# FLIGHT-CONTROLLER_VERSION_2.net
KiCad netlist of a schematic drawn in EasyEDA Pro
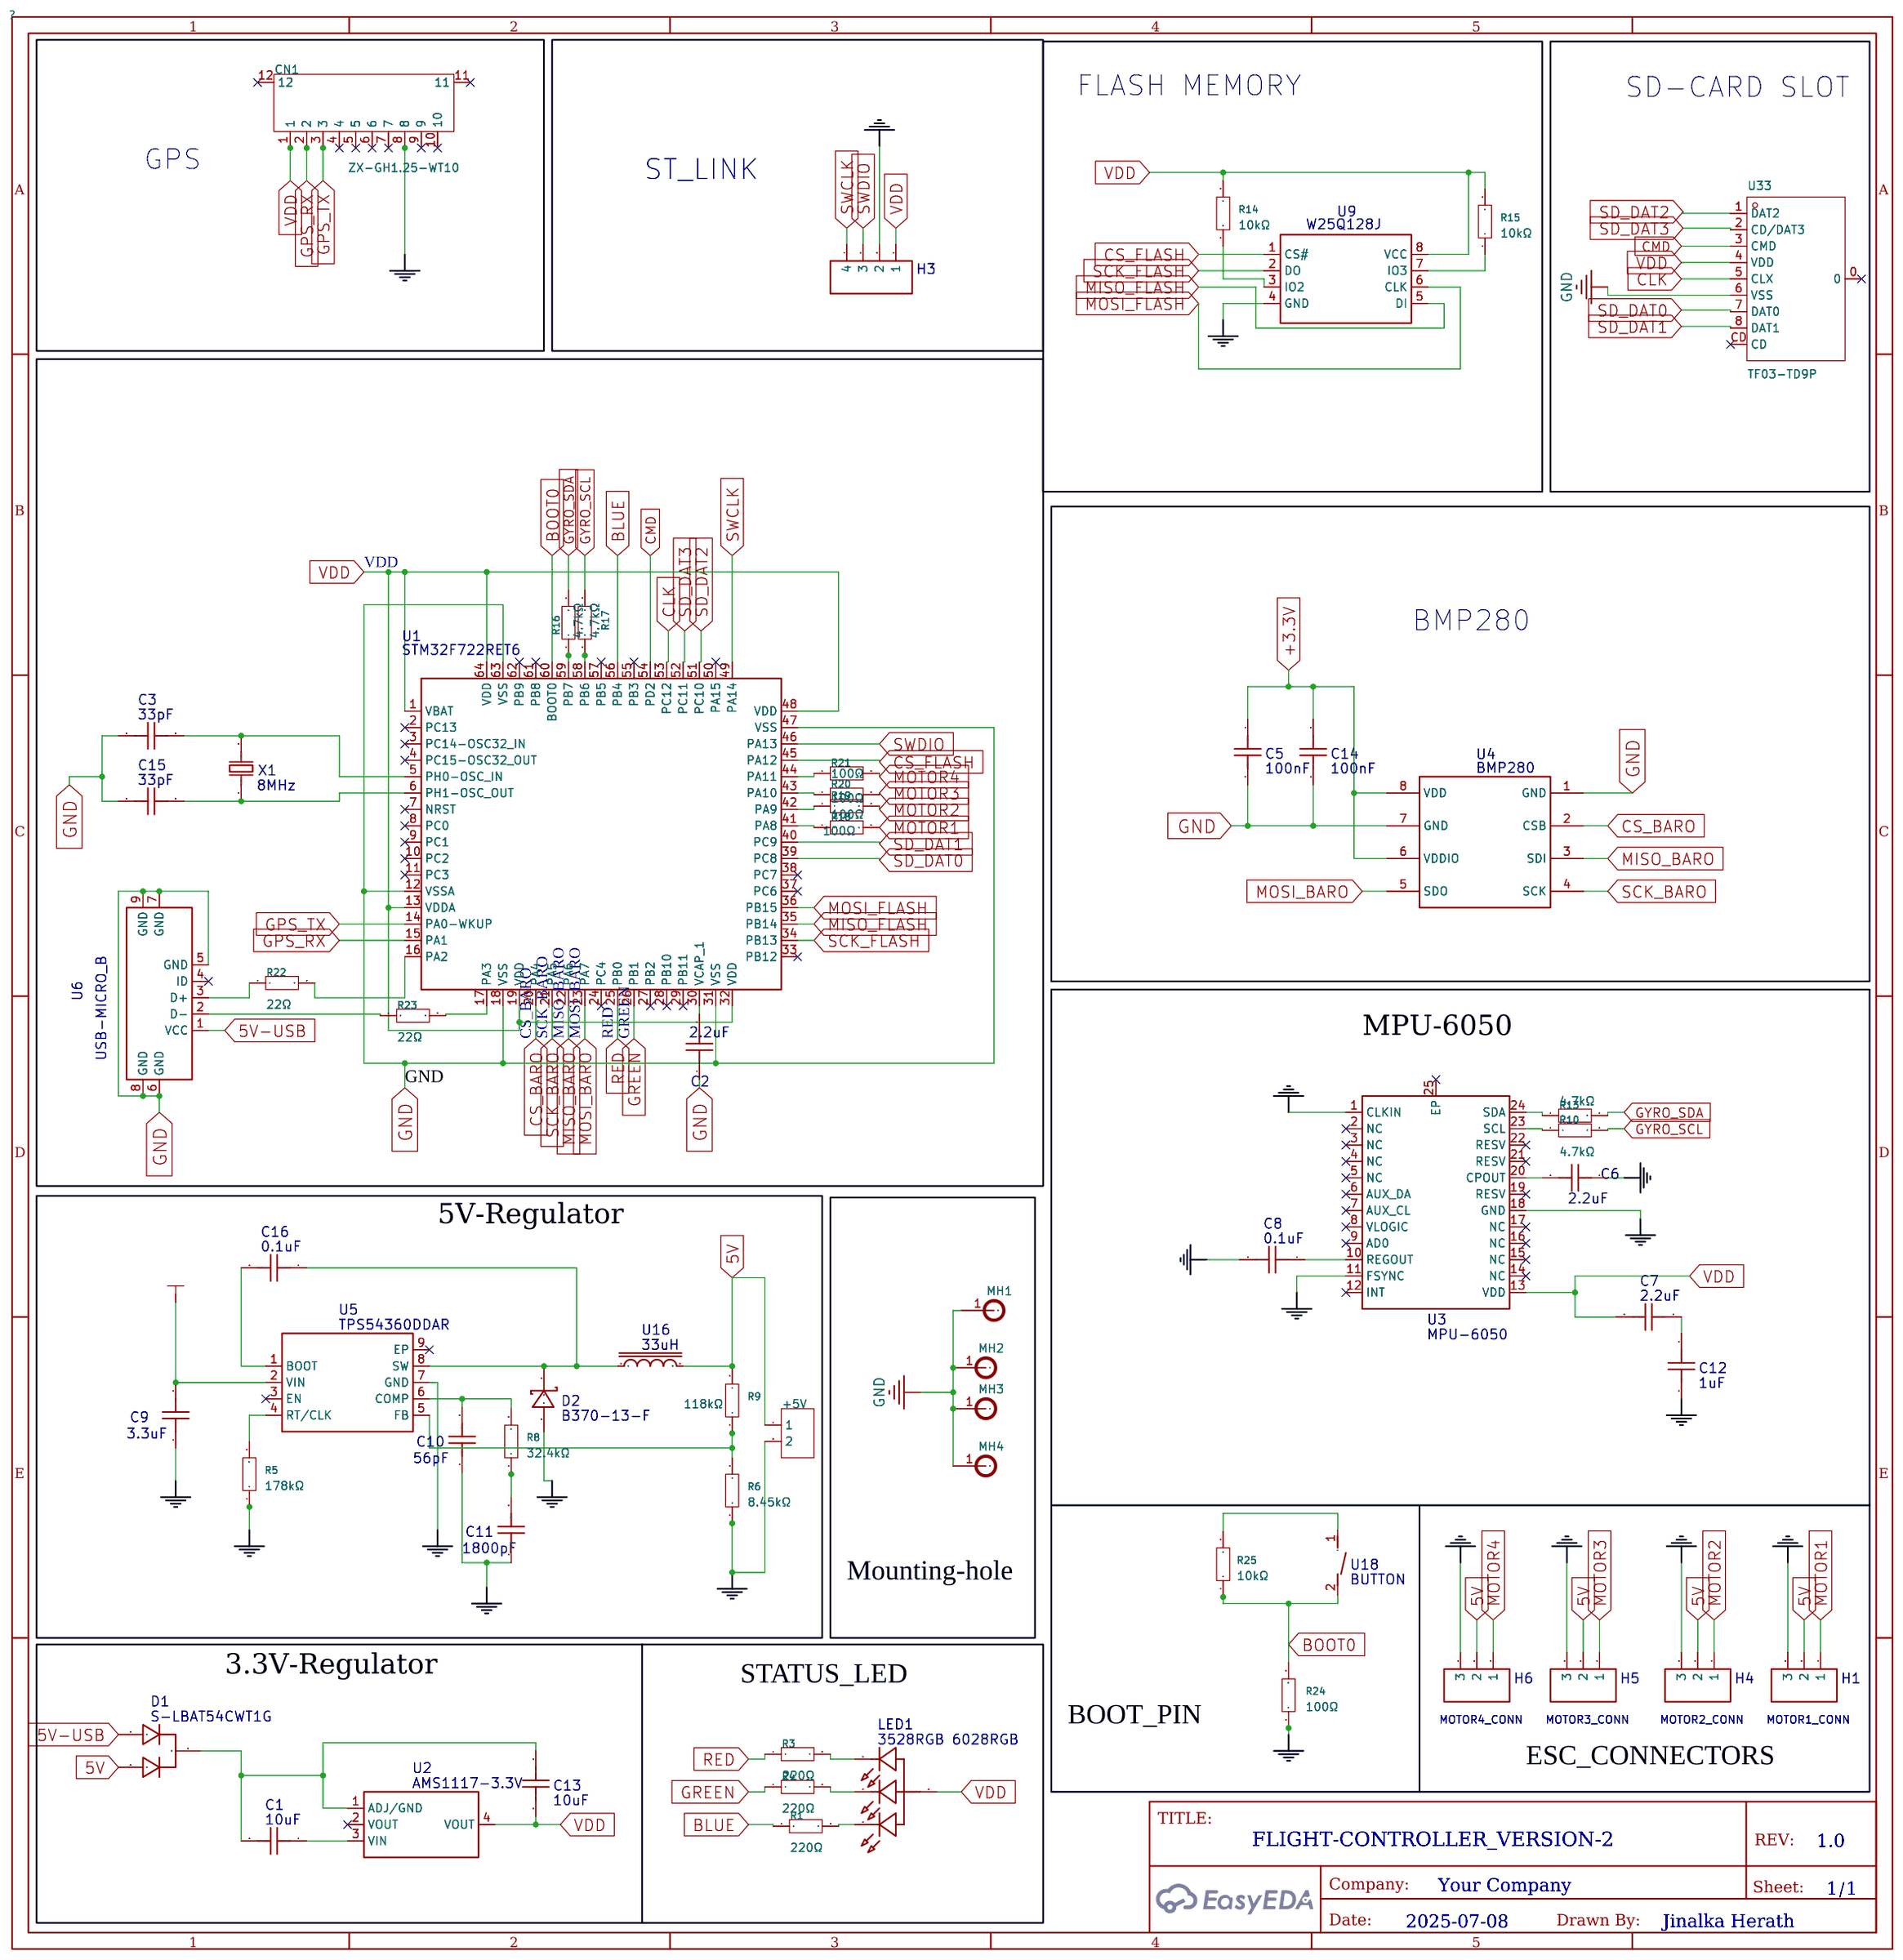
[diagram p0: schematic sheet]

(export (version "E")
  (design (tool "Eeschema 10.0.6"))
  (components
    (comp (ref "C1")
      (value "10uF")
      (footprint "easyedapro:C0603")
      (fields
        (field (name "Manufacturer Part") "C1608CH2A560J080AA")
        (field (name "Manufacturer") "TDK")
        (field (name "Contributor") "lcsc")
      )
      (libsource (lib "easyedapro") (part "10uF"))
    )
    (comp (ref "C2")
      (value "2.2uF")
      (footprint "easyedapro:CAP-SMD_L3.2-W2.5-1")
      (fields
        (field (name "Manufacturer Part") "25MU225MB23225")
        (field (name "Manufacturer") "rubycon(红宝石)")
        (field (name "Contributor") "lcsc")
      )
      (libsource (lib "easyedapro") (part "2.2uF"))
    )
    (comp (ref "C3")
      (value "33pF")
      (footprint "easyedapro:C0603")
      (fields
        (field (name "Manufacturer Part") "C1608CH2A560J080AA")
        (field (name "Manufacturer") "TDK")
        (field (name "Contributor") "lcsc")
      )
      (libsource (lib "easyedapro") (part "33pF"))
    )
    (comp (ref "C5")
      (value "100nF")
      (footprint "easyedapro:C0603")
      (fields
        (field (name "Manufacturer Part") "C1608CH2A560J080AA")
        (field (name "Manufacturer") "TDK")
        (field (name "Contributor") "lcsc")
      )
      (libsource (lib "easyedapro") (part "100nF"))
    )
    (comp (ref "C6")
      (value "2.2uF")
      (footprint "easyedapro:CAP-SMD_L3.2-W2.5-1")
      (fields
        (field (name "Manufacturer Part") "25MU225MB23225")
        (field (name "Manufacturer") "rubycon(红宝石)")
        (field (name "Contributor") "lcsc")
      )
      (libsource (lib "easyedapro") (part "2.2uF"))
    )
    (comp (ref "C7")
      (value "2.2uF")
      (footprint "easyedapro:CAP-SMD_L3.2-W2.5-1")
      (fields
        (field (name "Manufacturer Part") "25MU225MB23225")
        (field (name "Manufacturer") "rubycon(红宝石)")
        (field (name "Contributor") "lcsc")
      )
      (libsource (lib "easyedapro") (part "2.2uF"))
    )
    (comp (ref "C8")
      (value "0.1uF")
      (footprint "easyedapro:C0603")
      (fields
        (field (name "Manufacturer Part") "C1608CH2A560J080AA")
        (field (name "Manufacturer") "TDK")
        (field (name "Contributor") "lcsc")
      )
      (libsource (lib "easyedapro") (part "0.1uF"))
    )
    (comp (ref "C9")
      (value "3.3uF")
      (footprint "easyedapro:C0603")
      (fields
        (field (name "Manufacturer Part") "C1608CH2A560J080AA")
        (field (name "Manufacturer") "TDK")
        (field (name "Contributor") "lcsc")
      )
      (libsource (lib "easyedapro") (part "3.3uF"))
    )
    (comp (ref "C10")
      (value "56pF")
      (footprint "easyedapro:C0603")
      (fields
        (field (name "Manufacturer Part") "C1608CH2A560J080AA")
        (field (name "Manufacturer") "TDK")
        (field (name "Contributor") "lcsc")
      )
      (libsource (lib "easyedapro") (part "56pF"))
    )
    (comp (ref "C11")
      (value "1800pF")
      (footprint "easyedapro:C0603")
      (fields
        (field (name "Manufacturer Part") "C1608CH2A560J080AA")
        (field (name "Manufacturer") "TDK")
        (field (name "Contributor") "lcsc")
      )
      (libsource (lib "easyedapro") (part "1800pF"))
    )
    (comp (ref "C12")
      (value "1uF")
      (footprint "easyedapro:C0603")
      (fields
        (field (name "Manufacturer Part") "C1608CH2A560J080AA")
        (field (name "Manufacturer") "TDK")
        (field (name "Contributor") "lcsc")
      )
      (libsource (lib "easyedapro") (part "1uF"))
    )
    (comp (ref "C13")
      (value "10uF")
      (footprint "easyedapro:C0603")
      (fields
        (field (name "Manufacturer Part") "C1608CH2A560J080AA")
        (field (name "Manufacturer") "TDK")
        (field (name "Contributor") "lcsc")
      )
      (libsource (lib "easyedapro") (part "10uF"))
    )
    (comp (ref "C14")
      (value "100nF")
      (footprint "easyedapro:C0603")
      (fields
        (field (name "Manufacturer Part") "C1608CH2A560J080AA")
        (field (name "Manufacturer") "TDK")
        (field (name "Contributor") "lcsc")
      )
      (libsource (lib "easyedapro") (part "100nF"))
    )
    (comp (ref "C15")
      (value "33pF")
      (footprint "easyedapro:C0603")
      (fields
        (field (name "Manufacturer Part") "C1608CH2A560J080AA")
        (field (name "Manufacturer") "TDK")
        (field (name "Contributor") "lcsc")
      )
      (libsource (lib "easyedapro") (part "33pF"))
    )
    (comp (ref "C16")
      (value "0.1uF")
      (footprint "easyedapro:C0603")
      (fields
        (field (name "Manufacturer Part") "C1608CH2A560J080AA")
        (field (name "Manufacturer") "TDK")
        (field (name "Contributor") "lcsc")
      )
      (libsource (lib "easyedapro") (part "0.1uF"))
    )
    (comp (ref "CN1")
      (value "ZX-GH1.25-WT10")
      (footprint "easyedapro:CONN-SMD_ZX-GH1.25-WT10")
      (fields (field (name "Manufacturer") "Megastar(兆星)"))
      (libsource (lib "easyedapro") (part "ZX-GH1.25-WT10"))
    )
    (comp (ref "D1")
      (value "S-LBAT54CWT1G")
      (footprint "easyedapro:SC-70-3_L2.0-W1.3-P1.30-LS2.1-BR")
      (fields (field (name "Manufacturer") "LRC(乐山无线电)") (field (name "Contributor") "lcsc"))
      (libsource (lib "easyedapro") (part "S-LBAT54CWT1G"))
    )
    (comp (ref "D2")
      (value "B370-13-F")
      (footprint "easyedapro:SMC_L7.1-W6.2-LS8.1-RD")
      (fields (field (name "Manufacturer") "DIODES(美台)") (field (name "Contributor") "LCSC"))
      (libsource (lib "easyedapro") (part "B370-13-F"))
    )
    (comp (ref "H1")
      (value "MOTOR1_CONN")
      (footprint "easyedapro:HDR-F-2.54_1X3")
      (fields (field (name "Contributor") "LCEDA_Lib"))
      (libsource (lib "easyedapro") (part "MOTOR1_CONN"))
    )
    (comp (ref "H3")
      (value "ST_LINK")
      (footprint "easyedapro:HDR-F-2.54_1X4")
      (fields (field (name "Contributor") "LCEDA_Lib"))
      (libsource (lib "easyedapro") (part "ST_LINK"))
    )
    (comp (ref "H4")
      (value "MOTOR2_CONN")
      (footprint "easyedapro:HDR-F-2.54_1X3")
      (fields (field (name "Contributor") "LCEDA_Lib"))
      (libsource (lib "easyedapro") (part "MOTOR2_CONN"))
    )
    (comp (ref "H5")
      (value "MOTOR3_CONN")
      (footprint "easyedapro:HDR-F-2.54_1X3")
      (fields (field (name "Contributor") "LCEDA_Lib"))
      (libsource (lib "easyedapro") (part "MOTOR3_CONN"))
    )
    (comp (ref "H6")
      (value "MOTOR4_CONN")
      (footprint "easyedapro:HDR-F-2.54_1X3")
      (fields (field (name "Contributor") "LCEDA_Lib"))
      (libsource (lib "easyedapro") (part "MOTOR4_CONN"))
    )
    (comp (ref "H7")
      (value "+5V")
      (footprint "easyedapro:HDR-TH_2P-P2.54-V-F")
      (libsource (lib "easyedapro") (part "Header-Female-2.54_1x2"))
    )
    (comp (ref "LED1")
      (value "3528RGB 6028RGB")
      (footprint "easyedapro:LED-SMD_4P-L3.5-W2.8_3528RGB-6028RGB")
      (fields
        (field (name "Manufacturer Part") "3528反贴RGB 6028反贴RGB 缺口蓝色")
        (field (name "Contributor") "lcsc")
      )
      (libsource (lib "easyedapro") (part "3528RGB 6028RGB"))
    )
    (comp (ref "MH1")
      (value "~")
      (footprint "easyedapro:MH_7.5")
      (libsource (lib "easyedapro") (part "MH_7.5"))
    )
    (comp (ref "MH2")
      (value "~")
      (footprint "easyedapro:MH_7.5")
      (libsource (lib "easyedapro") (part "MH_7.5"))
    )
    (comp (ref "MH3")
      (value "~")
      (footprint "easyedapro:MH_7.5")
      (libsource (lib "easyedapro") (part "MH_7.5"))
    )
    (comp (ref "MH4")
      (value "~")
      (footprint "easyedapro:MH_7.5")
      (libsource (lib "easyedapro") (part "MH_7.5"))
    )
    (comp (ref "R1")
      (value "220Ω")
      (footprint "easyedapro:R0805")
      (fields
        (field (name "Manufacturer Part") "0805W8F2200T5E")
        (field (name "Manufacturer") "UNI-ROYAL(厚声)")
      )
      (libsource (lib "easyedapro") (part "0805W8F2200T5E"))
    )
    (comp (ref "R3")
      (value "220Ω")
      (footprint "easyedapro:R0805")
      (fields
        (field (name "Manufacturer Part") "0805W8F2200T5E")
        (field (name "Manufacturer") "UNI-ROYAL(厚声)")
      )
      (libsource (lib "easyedapro") (part "0805W8F2200T5E"))
    )
    (comp (ref "R4")
      (value "220Ω")
      (footprint "easyedapro:R0805")
      (fields
        (field (name "Manufacturer Part") "0805W8F2200T5E")
        (field (name "Manufacturer") "UNI-ROYAL(厚声)")
      )
      (libsource (lib "easyedapro") (part "0805W8F2200T5E"))
    )
    (comp (ref "R5")
      (value "178kΩ")
      (footprint "easyedapro:R0805")
      (fields
        (field (name "Manufacturer Part") "0805W8F2200T5E")
        (field (name "Manufacturer") "UNI-ROYAL(厚声)")
      )
      (libsource (lib "easyedapro") (part "0805W8F2200T5E"))
    )
    (comp (ref "R6")
      (value "8.45kΩ")
      (footprint "easyedapro:R0805")
      (fields
        (field (name "Manufacturer Part") "0805W8F2200T5E")
        (field (name "Manufacturer") "UNI-ROYAL(厚声)")
      )
      (libsource (lib "easyedapro") (part "0805W8F2200T5E"))
    )
    (comp (ref "R8")
      (value "32.4kΩ")
      (footprint "easyedapro:R0805")
      (fields
        (field (name "Manufacturer Part") "0805W8F2200T5E")
        (field (name "Manufacturer") "UNI-ROYAL(厚声)")
      )
      (libsource (lib "easyedapro") (part "0805W8F2200T5E"))
    )
    (comp (ref "R9")
      (value "118kΩ")
      (footprint "easyedapro:R0805")
      (fields
        (field (name "Manufacturer Part") "0805W8F2200T5E")
        (field (name "Manufacturer") "UNI-ROYAL(厚声)")
      )
      (libsource (lib "easyedapro") (part "0805W8F2200T5E"))
    )
    (comp (ref "R10")
      (value "4.7kΩ")
      (footprint "easyedapro:R0805")
      (fields
        (field (name "Manufacturer Part") "0805W8F2200T5E")
        (field (name "Manufacturer") "UNI-ROYAL(厚声)")
      )
      (libsource (lib "easyedapro") (part "0805W8F2200T5E"))
    )
    (comp (ref "R13")
      (value "4.7kΩ")
      (footprint "easyedapro:R0805")
      (fields
        (field (name "Manufacturer Part") "0805W8F2200T5E")
        (field (name "Manufacturer") "UNI-ROYAL(厚声)")
      )
      (libsource (lib "easyedapro") (part "0805W8F2200T5E"))
    )
    (comp (ref "R14")
      (value "10kΩ")
      (footprint "easyedapro:R0805")
      (fields
        (field (name "Manufacturer Part") "0805W8F2200T5E")
        (field (name "Manufacturer") "UNI-ROYAL(厚声)")
      )
      (libsource (lib "easyedapro") (part "0805W8F2200T5E"))
    )
    (comp (ref "R15")
      (value "10kΩ")
      (footprint "easyedapro:R0805")
      (fields
        (field (name "Manufacturer Part") "0805W8F2200T5E")
        (field (name "Manufacturer") "UNI-ROYAL(厚声)")
      )
      (libsource (lib "easyedapro") (part "0805W8F2200T5E"))
    )
    (comp (ref "R16")
      (value "4.7kΩ")
      (footprint "easyedapro:R0805")
      (fields
        (field (name "Manufacturer Part") "0805W8F2200T5E")
        (field (name "Manufacturer") "UNI-ROYAL(厚声)")
      )
      (libsource (lib "easyedapro") (part "0805W8F2200T5E"))
    )
    (comp (ref "R17")
      (value "4.7kΩ")
      (footprint "easyedapro:R0805")
      (fields
        (field (name "Manufacturer Part") "0805W8F2200T5E")
        (field (name "Manufacturer") "UNI-ROYAL(厚声)")
      )
      (libsource (lib "easyedapro") (part "0805W8F2200T5E"))
    )
    (comp (ref "R18")
      (value "100Ω")
      (footprint "easyedapro:R0805")
      (fields
        (field (name "Manufacturer Part") "0805W8F2200T5E")
        (field (name "Manufacturer") "UNI-ROYAL(厚声)")
      )
      (libsource (lib "easyedapro") (part "0805W8F2200T5E"))
    )
    (comp (ref "R19")
      (value "100Ω")
      (footprint "easyedapro:R0805")
      (fields
        (field (name "Manufacturer Part") "0805W8F2200T5E")
        (field (name "Manufacturer") "UNI-ROYAL(厚声)")
      )
      (libsource (lib "easyedapro") (part "0805W8F2200T5E"))
    )
    (comp (ref "R20")
      (value "100Ω")
      (footprint "easyedapro:R0805")
      (fields
        (field (name "Manufacturer Part") "0805W8F2200T5E")
        (field (name "Manufacturer") "UNI-ROYAL(厚声)")
      )
      (libsource (lib "easyedapro") (part "0805W8F2200T5E"))
    )
    (comp (ref "R21")
      (value "100Ω")
      (footprint "easyedapro:R0805")
      (fields
        (field (name "Manufacturer Part") "0805W8F2200T5E")
        (field (name "Manufacturer") "UNI-ROYAL(厚声)")
      )
      (libsource (lib "easyedapro") (part "0805W8F2200T5E"))
    )
    (comp (ref "R22")
      (value "22Ω")
      (footprint "easyedapro:R0805")
      (fields
        (field (name "Manufacturer Part") "0805W8F2200T5E")
        (field (name "Manufacturer") "UNI-ROYAL(厚声)")
      )
      (libsource (lib "easyedapro") (part "0805W8F2200T5E"))
    )
    (comp (ref "R23")
      (value "22Ω")
      (footprint "easyedapro:R0805")
      (fields
        (field (name "Manufacturer Part") "0805W8F2200T5E")
        (field (name "Manufacturer") "UNI-ROYAL(厚声)")
      )
      (libsource (lib "easyedapro") (part "0805W8F2200T5E"))
    )
    (comp (ref "R24")
      (value "100Ω")
      (footprint "easyedapro:R0805")
      (fields
        (field (name "Manufacturer Part") "0805W8F2200T5E")
        (field (name "Manufacturer") "UNI-ROYAL(厚声)")
      )
      (libsource (lib "easyedapro") (part "0805W8F2200T5E"))
    )
    (comp (ref "R25")
      (value "10kΩ")
      (footprint "easyedapro:R0805")
      (fields
        (field (name "Manufacturer Part") "0805W8F2200T5E")
        (field (name "Manufacturer") "UNI-ROYAL(厚声)")
      )
      (libsource (lib "easyedapro") (part "0805W8F2200T5E"))
    )
    (comp (ref "U1")
      (value "STM32F722RET6")
      (footprint "easyedapro:LQFP-64_L10.0-W10.0-P0.50-LS12.0-BL")
      (fields (field (name "Manufacturer") "ST(意法半导体)") (field (name "Contributor") "LCSC"))
      (libsource (lib "easyedapro") (part "STM32F722RET6"))
    )
    (comp (ref "U2")
      (value "AMS1117-3.3V")
      (footprint "easyedapro:SOT-223-4_L6.5-W3.5-P2.30-LS7.0-BR")
      (fields (field (name "Manufacturer") "WPMtek(维攀)") (field (name "Contributor") "LCSC"))
      (libsource (lib "easyedapro") (part "AMS1117-3.3V"))
    )
    (comp (ref "U3")
      (value "MPU-6050")
      (footprint "easyedapro:QFN-24_L4.0-W4.0-P0.50-BL-EP2.7")
      (fields (field (name "Manufacturer") "TDK InvenSense(应美盛)"))
      (libsource (lib "easyedapro") (part "MPU-6050_C24112"))
    )
    (comp (ref "U4")
      (value "BMP280")
      (footprint "easyedapro:LGA-8_L2.5-W2.0-P0.65_AMP6127")
      (fields (field (name "Manufacturer") "Bosch(博世)"))
      (libsource (lib "easyedapro") (part "BMP280"))
    )
    (comp (ref "U5")
      (value "TPS54360DDAR")
      (footprint "easyedapro:ESOP-8_L4.9-W3.9-P1.27-LS6.0-BL-EP")
      (fields
        (field (name "Manufacturer Part") "TPS54360DDAR(TOKMAS)")
        (field (name "Manufacturer") "Tokmas(托克马斯)")
        (field (name "Contributor") "lcsc")
      )
      (libsource (lib "easyedapro") (part "TPS54360DDAR(TOKMAS)"))
    )
    (comp (ref "U6")
      (value "USB-MICRO_B")
      (footprint "easyedapro:MICRO-USB-SMD_USB-MICRO_B")
      (fields (field (name "Contributor") "LCSC"))
      (libsource (lib "easyedapro") (part "USB-MICRO_B"))
    )
    (comp (ref "U9")
      (value "W25Q128J")
      (footprint "easyedapro:SOIC-8_L5.3-W5.3-P1.27-LS8.0-BL")
      (fields (field (name "Manufacturer Part") "W25Q128JVSIQ") (field (name "Manufacturer") "WINBOND(华邦)"))
      (libsource (lib "easyedapro") (part "W25Q128JVSIQTR"))
    )
    (comp (ref "U16")
      (value "33uH")
      (footprint "easyedapro:IND-SMD_L8.5-W8.0_SMS0850")
      (fields
        (field (name "Manufacturer Part") "SMS0850-330MT")
        (field (name "Manufacturer") "LanTu Micro(蓝图微电)")
        (field (name "Contributor") "lcsc")
      )
      (libsource (lib "easyedapro") (part "33uH"))
    )
    (comp (ref "U18")
      (value "BUTTON")
      (footprint "easyedapro:KEY-SMD_L6.0-W6.0-LS6.6")
      (fields (field (name "Contributor") "lcsc"))
      (libsource (lib "easyedapro") (part "BUTTON"))
    )
    (comp (ref "U33")
      (value "TF03-TD9P")
      (footprint "easyedapro:CONN-SMD_TF-001A-P")
      (fields (field (name "Manufacturer") "BXCONN(宝讯)"))
      (libsource (lib "easyedapro") (part "TF03-TD9P"))
    )
    (comp (ref "X1")
      (value "8MHz")
      (footprint "easyedapro:CRYSTAL-SMD_L3.2-W2.5_3225-8MHZ")
      (fields
        (field (name "Manufacturer Part") "X22EL89COI-111YLC-8M")
        (field (name "Manufacturer") "YXC(扬兴晶振)")
        (field (name "Contributor") "lcsc")
      )
      (libsource (lib "easyedapro") (part "8MHz"))
    )
  )
  (nets
    (net (code "1") (name "+3.3V") (class "Default")
      (node (ref "C14") (pin "1") (pinfunction "1_1") (pintype "unspecified"))
      (node (ref "C5") (pin "1") (pinfunction "1_1") (pintype "unspecified"))
      (node (ref "U4") (pin "6") (pinfunction "VDDIO_6") (pintype "unspecified"))
      (node (ref "U4") (pin "8") (pinfunction "VDD_8") (pintype "unspecified"))
    )
    (net (code "2") (name "+BATT") (class "Default")
      (node (ref "C9") (pin "2") (pinfunction "2_2") (pintype "unspecified"))
      (node (ref "U5") (pin "2") (pinfunction "VIN_2") (pintype "unspecified"))
    )
    (net (code "3") (name "5V") (class "Default")
      (node (ref "D1") (pin "2") (pinfunction "2_2") (pintype "unspecified"))
      (node (ref "H1") (pin "2") (pinfunction "2_2") (pintype "input"))
      (node (ref "H4") (pin "2") (pinfunction "2_2") (pintype "input"))
      (node (ref "H5") (pin "2") (pinfunction "2_2") (pintype "input"))
      (node (ref "H6") (pin "2") (pinfunction "2_2") (pintype "input"))
      (node (ref "H7") (pin "1") (pinfunction "1_1") (pintype "input"))
      (node (ref "R9") (pin "2") (pinfunction "2_2") (pintype "input"))
      (node (ref "U16") (pin "2") (pinfunction "2_2") (pintype "unspecified"))
    )
    (net (code "4") (name "5V-USB") (class "Default")
      (node (ref "D1") (pin "1") (pinfunction "1_1") (pintype "unspecified"))
      (node (ref "U6") (pin "1") (pinfunction "VCC_1") (pintype "unspecified"))
    )
    (net (code "5") (name "BLUE") (class "Default")
      (node (ref "R1") (pin "1") (pinfunction "1_1") (pintype "input"))
      (node (ref "U1") (pin "56") (pinfunction "PB4_56") (pintype "unspecified"))
    )
    (net (code "6") (name "BOOT0") (class "Default")
      (node (ref "R24") (pin "2") (pinfunction "2_2") (pintype "input"))
      (node (ref "R25") (pin "1") (pinfunction "1_1") (pintype "input"))
      (node (ref "U1") (pin "60") (pinfunction "BOOT0_60") (pintype "unspecified"))
      (node (ref "U18") (pin "2") (pinfunction "B_2") (pintype "unspecified"))
    )
    (net (code "7") (name "CLK") (class "Default")
      (node (ref "U1") (pin "53") (pinfunction "PC12_53") (pintype "unspecified"))
      (node (ref "U33") (pin "5") (pinfunction "CLX_5") (pintype "unspecified"))
    )
    (net (code "8") (name "CMD") (class "Default")
      (node (ref "U1") (pin "54") (pinfunction "PD2_54") (pintype "unspecified"))
      (node (ref "U33") (pin "3") (pinfunction "CMD_3") (pintype "unspecified"))
    )
    (net (code "9") (name "CS_BARO") (class "Default")
      (node (ref "U1") (pin "20") (pinfunction "PA4_20") (pintype "unspecified"))
      (node (ref "U4") (pin "2") (pinfunction "CSB_2") (pintype "unspecified"))
    )
    (net (code "10") (name "CS_FLASH") (class "Default")
      (node (ref "U1") (pin "45") (pinfunction "PA12_45") (pintype "unspecified"))
      (node (ref "U9") (pin "1") (pinfunction "CS#_1") (pintype "unspecified"))
    )
    (net (code "11") (name "GND") (class "Default")
      (node (ref "C10") (pin "1") (pinfunction "1_1") (pintype "unspecified"))
      (node (ref "C11") (pin "1") (pinfunction "1_1") (pintype "unspecified"))
      (node (ref "C12") (pin "2") (pinfunction "2_2") (pintype "unspecified"))
      (node (ref "C14") (pin "2") (pinfunction "2_2") (pintype "unspecified"))
      (node (ref "C15") (pin "1") (pinfunction "1_1") (pintype "unspecified"))
      (node (ref "C2") (pin "1") (pinfunction "1_1") (pintype "unspecified"))
      (node (ref "C3") (pin "1") (pinfunction "1_1") (pintype "unspecified"))
      (node (ref "C5") (pin "2") (pinfunction "2_2") (pintype "unspecified"))
      (node (ref "C6") (pin "1") (pinfunction "1_1") (pintype "unspecified"))
      (node (ref "C8") (pin "2") (pinfunction "2_2") (pintype "unspecified"))
      (node (ref "C9") (pin "1") (pinfunction "1_1") (pintype "unspecified"))
      (node (ref "CN1") (pin "8") (pinfunction "8_8") (pintype "unspecified"))
      (node (ref "D2") (pin "2") (pinfunction "A_2") (pintype "unspecified"))
      (node (ref "H1") (pin "3") (pinfunction "3_3") (pintype "input"))
      (node (ref "H3") (pin "2") (pinfunction "2_2") (pintype "unspecified"))
      (node (ref "H4") (pin "3") (pinfunction "3_3") (pintype "input"))
      (node (ref "H5") (pin "3") (pinfunction "3_3") (pintype "input"))
      (node (ref "H6") (pin "3") (pinfunction "3_3") (pintype "input"))
      (node (ref "H7") (pin "2") (pinfunction "2_2") (pintype "input"))
      (node (ref "MH1") (pin "1") (pinfunction "1_1") (pintype "input"))
      (node (ref "MH2") (pin "1") (pinfunction "1_1") (pintype "input"))
      (node (ref "MH3") (pin "1") (pinfunction "1_1") (pintype "input"))
      (node (ref "MH4") (pin "1") (pinfunction "1_1") (pintype "input"))
      (node (ref "R24") (pin "1") (pinfunction "1_1") (pintype "input"))
      (node (ref "R5") (pin "1") (pinfunction "1_1") (pintype "input"))
      (node (ref "R6") (pin "1") (pinfunction "1_1") (pintype "input"))
      (node (ref "U1") (pin "12") (pinfunction "VSSA_12") (pintype "unspecified"))
      (node (ref "U1") (pin "18") (pinfunction "VSS_18") (pintype "unspecified"))
      (node (ref "U1") (pin "31") (pinfunction "VSS_31") (pintype "unspecified"))
      (node (ref "U1") (pin "47") (pinfunction "VSS_47") (pintype "unspecified"))
      (node (ref "U1") (pin "63") (pinfunction "VSS_63") (pintype "unspecified"))
      (node (ref "U3") (pin "1") (pinfunction "CLKIN_1") (pintype "unspecified"))
      (node (ref "U3") (pin "11") (pinfunction "FSYNC_11") (pintype "unspecified"))
      (node (ref "U3") (pin "18") (pinfunction "GND_18") (pintype "unspecified"))
      (node (ref "U33") (pin "6") (pinfunction "VSS_6") (pintype "unspecified"))
      (node (ref "U4") (pin "1") (pinfunction "GND_1") (pintype "unspecified"))
      (node (ref "U4") (pin "7") (pinfunction "GND_7") (pintype "unspecified"))
      (node (ref "U5") (pin "7") (pinfunction "GND_7") (pintype "unspecified"))
      (node (ref "U6") (pin "5") (pinfunction "GND_5") (pintype "unspecified"))
      (node (ref "U6") (pin "6") (pinfunction "GND_6") (pintype "unspecified"))
      (node (ref "U6") (pin "7") (pinfunction "GND_7") (pintype "unspecified"))
      (node (ref "U6") (pin "8") (pinfunction "GND_8") (pintype "unspecified"))
      (node (ref "U6") (pin "9") (pinfunction "GND_9") (pintype "unspecified"))
      (node (ref "U9") (pin "4") (pinfunction "GND_4") (pintype "unspecified"))
    )
    (net (code "12") (name "GPS_RX") (class "Default")
      (node (ref "CN1") (pin "2") (pinfunction "2_2") (pintype "unspecified"))
      (node (ref "U1") (pin "15") (pinfunction "PA1_15") (pintype "unspecified"))
    )
    (net (code "13") (name "GPS_TX") (class "Default")
      (node (ref "CN1") (pin "3") (pinfunction "3_3") (pintype "unspecified"))
      (node (ref "U1") (pin "14") (pinfunction "PA0-WKUP_14") (pintype "unspecified"))
    )
    (net (code "14") (name "GREEN") (class "Default")
      (node (ref "R4") (pin "1") (pinfunction "1_1") (pintype "input"))
      (node (ref "U1") (pin "26") (pinfunction "PB1_26") (pintype "unspecified"))
    )
    (net (code "15") (name "GYRO_SCL") (class "Default")
      (node (ref "R10") (pin "2") (pinfunction "2_2") (pintype "input"))
      (node (ref "R17") (pin "2") (pinfunction "2_2") (pintype "input"))
    )
    (net (code "16") (name "GYRO_SDA") (class "Default")
      (node (ref "R13") (pin "2") (pinfunction "2_2") (pintype "input"))
      (node (ref "R16") (pin "2") (pinfunction "2_2") (pintype "input"))
    )
    (net (code "17") (name "MISO_BARO") (class "Default")
      (node (ref "U1") (pin "22") (pinfunction "PA6_22") (pintype "unspecified"))
      (node (ref "U4") (pin "3") (pinfunction "SDI_3") (pintype "unspecified"))
    )
    (net (code "18") (name "MISO_FLASH") (class "Default")
      (node (ref "U1") (pin "35") (pinfunction "PB14_35") (pintype "unspecified"))
      (node (ref "U9") (pin "5") (pinfunction "DI_5") (pintype "unspecified"))
    )
    (net (code "19") (name "MOSI_BARO") (class "Default")
      (node (ref "U1") (pin "23") (pinfunction "PA7_23") (pintype "unspecified"))
      (node (ref "U4") (pin "5") (pinfunction "SDO_5") (pintype "unspecified"))
    )
    (net (code "20") (name "MOSI_FLASH") (class "Default")
      (node (ref "U1") (pin "36") (pinfunction "PB15_36") (pintype "unspecified"))
      (node (ref "U9") (pin "6") (pinfunction "CLK_6") (pintype "unspecified"))
    )
    (net (code "21") (name "MOTOR1") (class "Default")
      (node (ref "H1") (pin "1") (pinfunction "1_1") (pintype "input"))
      (node (ref "R18") (pin "2") (pinfunction "2_2") (pintype "input"))
    )
    (net (code "22") (name "MOTOR2") (class "Default")
      (node (ref "H4") (pin "1") (pinfunction "1_1") (pintype "input"))
      (node (ref "R19") (pin "2") (pinfunction "2_2") (pintype "input"))
    )
    (net (code "23") (name "MOTOR3") (class "Default")
      (node (ref "H5") (pin "1") (pinfunction "1_1") (pintype "input"))
      (node (ref "R20") (pin "2") (pinfunction "2_2") (pintype "input"))
    )
    (net (code "24") (name "MOTOR4") (class "Default")
      (node (ref "H6") (pin "1") (pinfunction "1_1") (pintype "input"))
      (node (ref "R21") (pin "2") (pinfunction "2_2") (pintype "input"))
    )
    (net (code "25") (name "Net-(C11-Pad2)") (class "Default")
      (node (ref "C11") (pin "2") (pinfunction "2_2") (pintype "unspecified"))
      (node (ref "R8") (pin "1") (pinfunction "1_1") (pintype "input"))
    )
    (net (code "26") (name "Net-(C12-Pad1)") (class "Default")
      (node (ref "C12") (pin "1") (pinfunction "1_1") (pintype "unspecified"))
      (node (ref "C7") (pin "1") (pinfunction "1_1") (pintype "unspecified"))
    )
    (net (code "27") (name "Net-(D2-C)") (class "Default")
      (node (ref "C16") (pin "1") (pinfunction "1_1") (pintype "unspecified"))
      (node (ref "D2") (pin "1") (pinfunction "C_1") (pintype "unspecified"))
      (node (ref "U16") (pin "1") (pinfunction "1_1") (pintype "unspecified"))
      (node (ref "U5") (pin "8") (pinfunction "SW_8") (pintype "unspecified"))
    )
    (net (code "28") (name "Net-(LED1-B)") (class "Default")
      (node (ref "LED1") (pin "1") (pinfunction "B_1") (pintype "unspecified"))
      (node (ref "R4") (pin "2") (pinfunction "2_2") (pintype "input"))
    )
    (net (code "29") (name "Net-(LED1-G)") (class "Default")
      (node (ref "LED1") (pin "4") (pinfunction "G_4") (pintype "unspecified"))
      (node (ref "R1") (pin "2") (pinfunction "2_2") (pintype "input"))
    )
    (net (code "30") (name "Net-(LED1-R)") (class "Default")
      (node (ref "LED1") (pin "2") (pinfunction "R_2") (pintype "unspecified"))
      (node (ref "R3") (pin "2") (pinfunction "2_2") (pintype "input"))
    )
    (net (code "31") (name "Net-(U1-PA2)") (class "Default")
      (node (ref "R22") (pin "2") (pinfunction "2_2") (pintype "input"))
      (node (ref "U1") (pin "16") (pinfunction "PA2_16") (pintype "unspecified"))
    )
    (net (code "32") (name "Net-(U1-PA3)") (class "Default")
      (node (ref "R23") (pin "2") (pinfunction "2_2") (pintype "input"))
      (node (ref "U1") (pin "17") (pinfunction "PA3_17") (pintype "unspecified"))
    )
    (net (code "33") (name "Net-(U1-PA8)") (class "Default")
      (node (ref "R18") (pin "1") (pinfunction "1_1") (pintype "input"))
      (node (ref "U1") (pin "41") (pinfunction "PA8_41") (pintype "unspecified"))
    )
    (net (code "34") (name "Net-(U1-PA9)") (class "Default")
      (node (ref "R19") (pin "1") (pinfunction "1_1") (pintype "input"))
      (node (ref "U1") (pin "42") (pinfunction "PA9_42") (pintype "unspecified"))
    )
    (net (code "35") (name "Net-(U1-PA10)") (class "Default")
      (node (ref "R20") (pin "1") (pinfunction "1_1") (pintype "input"))
      (node (ref "U1") (pin "43") (pinfunction "PA10_43") (pintype "unspecified"))
    )
    (net (code "36") (name "Net-(U1-PA11)") (class "Default")
      (node (ref "R21") (pin "1") (pinfunction "1_1") (pintype "input"))
      (node (ref "U1") (pin "44") (pinfunction "PA11_44") (pintype "unspecified"))
    )
    (net (code "37") (name "Net-(U1-PB6)") (class "Default")
      (node (ref "R17") (pin "1") (pinfunction "1_1") (pintype "input"))
      (node (ref "U1") (pin "58") (pinfunction "PB6_58") (pintype "unspecified"))
    )
    (net (code "38") (name "Net-(U1-PB7)") (class "Default")
      (node (ref "R16") (pin "1") (pinfunction "1_1") (pintype "input"))
      (node (ref "U1") (pin "59") (pinfunction "PB7_59") (pintype "unspecified"))
    )
    (net (code "39") (name "Net-(U1-PH0-OSC_IN)") (class "Default")
      (node (ref "C3") (pin "2") (pinfunction "2_2") (pintype "unspecified"))
      (node (ref "U1") (pin "5") (pinfunction "PH0-OSC_IN_5") (pintype "unspecified"))
      (node (ref "X1") (pin "2") (pinfunction "2_2") (pintype "unspecified"))
    )
    (net (code "40") (name "Net-(U1-PH1-OSC_OUT)") (class "Default")
      (node (ref "C15") (pin "2") (pinfunction "2_2") (pintype "unspecified"))
      (node (ref "U1") (pin "6") (pinfunction "PH1-OSC_OUT_6") (pintype "unspecified"))
      (node (ref "X1") (pin "1") (pinfunction "1_1") (pintype "unspecified"))
    )
    (net (code "41") (name "Net-(U1-VCAP_1)") (class "Default")
      (node (ref "C2") (pin "2") (pinfunction "2_2") (pintype "unspecified"))
      (node (ref "U1") (pin "30") (pinfunction "VCAP_1_30") (pintype "unspecified"))
    )
    (net (code "42") (name "Net-(U2-ADJ{slash}GND)") (class "Default")
      (node (ref "C1") (pin "2") (pinfunction "2_2") (pintype "unspecified"))
      (node (ref "C13") (pin "1") (pinfunction "1_1") (pintype "unspecified"))
      (node (ref "D1") (pin "3") (pinfunction "3_3") (pintype "unspecified"))
      (node (ref "U2") (pin "1") (pinfunction "ADJ/GND_1") (pintype "unspecified"))
    )
    (net (code "43") (name "Net-(U2-VIN)") (class "Default")
      (node (ref "C1") (pin "1") (pinfunction "1_1") (pintype "unspecified"))
      (node (ref "U2") (pin "3") (pinfunction "VIN_3") (pintype "unspecified"))
    )
    (net (code "44") (name "Net-(U3-CPOUT)") (class "Default")
      (node (ref "C6") (pin "2") (pinfunction "2_2") (pintype "unspecified"))
      (node (ref "U3") (pin "20") (pinfunction "CPOUT_20") (pintype "unspecified"))
    )
    (net (code "45") (name "Net-(U3-REGOUT)") (class "Default")
      (node (ref "C8") (pin "1") (pinfunction "1_1") (pintype "unspecified"))
      (node (ref "U3") (pin "10") (pinfunction "REGOUT_10") (pintype "unspecified"))
    )
    (net (code "46") (name "Net-(U3-SCL)") (class "Default")
      (node (ref "R10") (pin "1") (pinfunction "1_1") (pintype "input"))
      (node (ref "U3") (pin "23") (pinfunction "SCL_23") (pintype "unspecified"))
    )
    (net (code "47") (name "Net-(U3-SDA)") (class "Default")
      (node (ref "R13") (pin "1") (pinfunction "1_1") (pintype "input"))
      (node (ref "U3") (pin "24") (pinfunction "SDA_24") (pintype "unspecified"))
    )
    (net (code "48") (name "Net-(U5-BOOT)") (class "Default")
      (node (ref "C16") (pin "2") (pinfunction "2_2") (pintype "unspecified"))
      (node (ref "U5") (pin "1") (pinfunction "BOOT_1") (pintype "unspecified"))
    )
    (net (code "49") (name "Net-(U5-COMP)") (class "Default")
      (node (ref "C10") (pin "2") (pinfunction "2_2") (pintype "unspecified"))
      (node (ref "R8") (pin "2") (pinfunction "2_2") (pintype "input"))
      (node (ref "U5") (pin "6") (pinfunction "COMP_6") (pintype "unspecified"))
    )
    (net (code "50") (name "Net-(U5-FB)") (class "Default")
      (node (ref "R6") (pin "2") (pinfunction "2_2") (pintype "input"))
      (node (ref "R9") (pin "1") (pinfunction "1_1") (pintype "input"))
      (node (ref "U5") (pin "5") (pinfunction "FB_5") (pintype "unspecified"))
    )
    (net (code "51") (name "Net-(U5-RT{slash}CLK)") (class "Default")
      (node (ref "R5") (pin "2") (pinfunction "2_2") (pintype "input"))
      (node (ref "U5") (pin "4") (pinfunction "RT/CLK_4") (pintype "unspecified"))
    )
    (net (code "52") (name "Net-(U6-D+)") (class "Default")
      (node (ref "R22") (pin "1") (pinfunction "1_1") (pintype "input"))
      (node (ref "U6") (pin "3") (pinfunction "D+_3") (pintype "unspecified"))
    )
    (net (code "53") (name "Net-(U6-D-)") (class "Default")
      (node (ref "R23") (pin "1") (pinfunction "1_1") (pintype "input"))
      (node (ref "U6") (pin "2") (pinfunction "D-_2") (pintype "unspecified"))
    )
    (net (code "54") (name "Net-(U9-IO2)") (class "Default")
      (node (ref "R14") (pin "1") (pinfunction "1_1") (pintype "input"))
      (node (ref "U9") (pin "3") (pinfunction "IO2_3") (pintype "unspecified"))
    )
    (net (code "55") (name "Net-(U9-IO3)") (class "Default")
      (node (ref "R15") (pin "1") (pinfunction "1_1") (pintype "input"))
      (node (ref "U9") (pin "7") (pinfunction "IO3_7") (pintype "unspecified"))
    )
    (net (code "56") (name "Net-(U18-A)") (class "Default")
      (node (ref "R25") (pin "2") (pinfunction "2_2") (pintype "input"))
      (node (ref "U18") (pin "1") (pinfunction "A_1") (pintype "unspecified"))
    )
    (net (code "57") (name "RED") (class "Default")
      (node (ref "R3") (pin "1") (pinfunction "1_1") (pintype "input"))
      (node (ref "U1") (pin "25") (pinfunction "PB0_25") (pintype "unspecified"))
    )
    (net (code "58") (name "SCK_BARO") (class "Default")
      (node (ref "U1") (pin "21") (pinfunction "PA5_21") (pintype "unspecified"))
      (node (ref "U4") (pin "4") (pinfunction "SCK_4") (pintype "unspecified"))
    )
    (net (code "59") (name "SCK_FLASH") (class "Default")
      (node (ref "U1") (pin "34") (pinfunction "PB13_34") (pintype "unspecified"))
      (node (ref "U9") (pin "2") (pinfunction "DO_2") (pintype "unspecified"))
    )
    (net (code "60") (name "SD_DAT0") (class "Default")
      (node (ref "U1") (pin "39") (pinfunction "PC8_39") (pintype "unspecified"))
      (node (ref "U33") (pin "7") (pinfunction "DAT0_7") (pintype "unspecified"))
    )
    (net (code "61") (name "SD_DAT1") (class "Default")
      (node (ref "U1") (pin "40") (pinfunction "PC9_40") (pintype "unspecified"))
      (node (ref "U33") (pin "8") (pinfunction "DAT1_8") (pintype "unspecified"))
    )
    (net (code "62") (name "SD_DAT2") (class "Default")
      (node (ref "U1") (pin "51") (pinfunction "PC10_51") (pintype "unspecified"))
      (node (ref "U33") (pin "1") (pinfunction "DAT2_1") (pintype "unspecified"))
    )
    (net (code "63") (name "SD_DAT3") (class "Default")
      (node (ref "U1") (pin "52") (pinfunction "PC11_52") (pintype "unspecified"))
      (node (ref "U33") (pin "2") (pinfunction "CD/DAT3_2") (pintype "unspecified"))
    )
    (net (code "64") (name "SWCLK") (class "Default")
      (node (ref "H3") (pin "4") (pinfunction "4_4") (pintype "unspecified"))
      (node (ref "U1") (pin "49") (pinfunction "PA14_49") (pintype "unspecified"))
    )
    (net (code "65") (name "SWDIO") (class "Default")
      (node (ref "H3") (pin "3") (pinfunction "3_3") (pintype "unspecified"))
      (node (ref "U1") (pin "46") (pinfunction "PA13_46") (pintype "unspecified"))
    )
    (net (code "66") (name "VDD") (class "Default")
      (node (ref "C13") (pin "2") (pinfunction "2_2") (pintype "unspecified"))
      (node (ref "C7") (pin "2") (pinfunction "2_2") (pintype "unspecified"))
      (node (ref "CN1") (pin "1") (pinfunction "1_1") (pintype "unspecified"))
      (node (ref "H3") (pin "1") (pinfunction "1_1") (pintype "unspecified"))
      (node (ref "LED1") (pin "3") (pinfunction "A_3") (pintype "unspecified"))
      (node (ref "R14") (pin "2") (pinfunction "2_2") (pintype "input"))
      (node (ref "R15") (pin "2") (pinfunction "2_2") (pintype "input"))
      (node (ref "U1") (pin "1") (pinfunction "VBAT_1") (pintype "unspecified"))
      (node (ref "U1") (pin "13") (pinfunction "VDDA_13") (pintype "unspecified"))
      (node (ref "U1") (pin "19") (pinfunction "VDD_19") (pintype "unspecified"))
      (node (ref "U1") (pin "32") (pinfunction "VDD_32") (pintype "unspecified"))
      (node (ref "U1") (pin "48") (pinfunction "VDD_48") (pintype "unspecified"))
      (node (ref "U1") (pin "64") (pinfunction "VDD_64") (pintype "unspecified"))
      (node (ref "U2") (pin "4") (pinfunction "VOUT_4") (pintype "unspecified"))
      (node (ref "U3") (pin "13") (pinfunction "VDD_13") (pintype "unspecified"))
      (node (ref "U33") (pin "4") (pinfunction "VDD_4") (pintype "unspecified"))
      (node (ref "U9") (pin "8") (pinfunction "VCC_8") (pintype "unspecified"))
    )
    (net (code "67") (name "unconnected-(CN1-Pad4)") (class "Default")
      (node (ref "CN1") (pin "4") (pinfunction "4_4") (pintype "unspecified+no_connect"))
    )
    (net (code "68") (name "unconnected-(CN1-Pad5)") (class "Default")
      (node (ref "CN1") (pin "5") (pinfunction "5_5") (pintype "unspecified+no_connect"))
    )
    (net (code "69") (name "unconnected-(CN1-Pad6)") (class "Default")
      (node (ref "CN1") (pin "6") (pinfunction "6_6") (pintype "unspecified+no_connect"))
    )
    (net (code "70") (name "unconnected-(CN1-Pad7)") (class "Default")
      (node (ref "CN1") (pin "7") (pinfunction "7_7") (pintype "unspecified+no_connect"))
    )
    (net (code "71") (name "unconnected-(CN1-Pad9)") (class "Default")
      (node (ref "CN1") (pin "9") (pinfunction "9_9") (pintype "unspecified+no_connect"))
    )
    (net (code "72") (name "unconnected-(CN1-Pad10)") (class "Default")
      (node (ref "CN1") (pin "10") (pinfunction "10_10") (pintype "unspecified+no_connect"))
    )
    (net (code "73") (name "unconnected-(CN1-Pad11)") (class "Default")
      (node (ref "CN1") (pin "11") (pinfunction "11_11") (pintype "unspecified+no_connect"))
    )
    (net (code "74") (name "unconnected-(CN1-Pad12)") (class "Default")
      (node (ref "CN1") (pin "12") (pinfunction "12_12") (pintype "unspecified+no_connect"))
    )
    (net (code "75") (name "unconnected-(U1-NRST-Pad7)") (class "Default")
      (node (ref "U1") (pin "7") (pinfunction "NRST_7") (pintype "unspecified+no_connect"))
    )
    (net (code "76") (name "unconnected-(U1-PA15-Pad50)") (class "Default")
      (node (ref "U1") (pin "50") (pinfunction "PA15_50") (pintype "unspecified+no_connect"))
    )
    (net (code "77") (name "unconnected-(U1-PB2-Pad27)") (class "Default")
      (node (ref "U1") (pin "27") (pinfunction "PB2_27") (pintype "unspecified+no_connect"))
    )
    (net (code "78") (name "unconnected-(U1-PB3-Pad55)") (class "Default")
      (node (ref "U1") (pin "55") (pinfunction "PB3_55") (pintype "unspecified+no_connect"))
    )
    (net (code "79") (name "unconnected-(U1-PB5-Pad57)") (class "Default")
      (node (ref "U1") (pin "57") (pinfunction "PB5_57") (pintype "unspecified+no_connect"))
    )
    (net (code "80") (name "unconnected-(U1-PB8-Pad61)") (class "Default")
      (node (ref "U1") (pin "61") (pinfunction "PB8_61") (pintype "unspecified+no_connect"))
    )
    (net (code "81") (name "unconnected-(U1-PB9-Pad62)") (class "Default")
      (node (ref "U1") (pin "62") (pinfunction "PB9_62") (pintype "unspecified+no_connect"))
    )
    (net (code "82") (name "unconnected-(U1-PB10-Pad28)") (class "Default")
      (node (ref "U1") (pin "28") (pinfunction "PB10_28") (pintype "unspecified+no_connect"))
    )
    (net (code "83") (name "unconnected-(U1-PB11-Pad29)") (class "Default")
      (node (ref "U1") (pin "29") (pinfunction "PB11_29") (pintype "unspecified+no_connect"))
    )
    (net (code "84") (name "unconnected-(U1-PB12-Pad33)") (class "Default")
      (node (ref "U1") (pin "33") (pinfunction "PB12_33") (pintype "unspecified+no_connect"))
    )
    (net (code "85") (name "unconnected-(U1-PC0-Pad8)") (class "Default")
      (node (ref "U1") (pin "8") (pinfunction "PC0_8") (pintype "unspecified+no_connect"))
    )
    (net (code "86") (name "unconnected-(U1-PC1-Pad9)") (class "Default")
      (node (ref "U1") (pin "9") (pinfunction "PC1_9") (pintype "unspecified+no_connect"))
    )
    (net (code "87") (name "unconnected-(U1-PC2-Pad10)") (class "Default")
      (node (ref "U1") (pin "10") (pinfunction "PC2_10") (pintype "unspecified+no_connect"))
    )
    (net (code "88") (name "unconnected-(U1-PC3-Pad11)") (class "Default")
      (node (ref "U1") (pin "11") (pinfunction "PC3_11") (pintype "unspecified+no_connect"))
    )
    (net (code "89") (name "unconnected-(U1-PC4-Pad24)") (class "Default")
      (node (ref "U1") (pin "24") (pinfunction "PC4_24") (pintype "unspecified+no_connect"))
    )
    (net (code "90") (name "unconnected-(U1-PC6-Pad37)") (class "Default")
      (node (ref "U1") (pin "37") (pinfunction "PC6_37") (pintype "unspecified+no_connect"))
    )
    (net (code "91") (name "unconnected-(U1-PC7-Pad38)") (class "Default")
      (node (ref "U1") (pin "38") (pinfunction "PC7_38") (pintype "unspecified+no_connect"))
    )
    (net (code "92") (name "unconnected-(U1-PC13-Pad2)") (class "Default")
      (node (ref "U1") (pin "2") (pinfunction "PC13_2") (pintype "unspecified+no_connect"))
    )
    (net (code "93") (name "unconnected-(U1-PC14-OSC32_IN-Pad3)") (class "Default")
      (node (ref "U1") (pin "3") (pinfunction "PC14-OSC32_IN_3") (pintype "unspecified+no_connect"))
    )
    (net (code "94") (name "unconnected-(U1-PC15-OSC32_OUT-Pad4)") (class "Default")
      (node (ref "U1") (pin "4") (pinfunction "PC15-OSC32_OUT_4") (pintype "unspecified+no_connect"))
    )
    (net (code "95") (name "unconnected-(U2-VOUT-Pad2)") (class "Default")
      (node (ref "U2") (pin "2") (pinfunction "VOUT_2") (pintype "unspecified+no_connect"))
    )
    (net (code "96") (name "unconnected-(U3-AD0-Pad9)") (class "Default")
      (node (ref "U3") (pin "9") (pinfunction "AD0_9") (pintype "unspecified+no_connect"))
    )
    (net (code "97") (name "unconnected-(U3-AUX_CL-Pad7)") (class "Default")
      (node (ref "U3") (pin "7") (pinfunction "AUX_CL_7") (pintype "unspecified+no_connect"))
    )
    (net (code "98") (name "unconnected-(U3-AUX_DA-Pad6)") (class "Default")
      (node (ref "U3") (pin "6") (pinfunction "AUX_DA_6") (pintype "unspecified+no_connect"))
    )
    (net (code "99") (name "unconnected-(U3-EP-Pad25)") (class "Default")
      (node (ref "U3") (pin "25") (pinfunction "EP_25") (pintype "unspecified+no_connect"))
    )
    (net (code "100") (name "unconnected-(U3-INT-Pad12)") (class "Default")
      (node (ref "U3") (pin "12") (pinfunction "INT_12") (pintype "unspecified+no_connect"))
    )
    (net (code "101") (name "unconnected-(U3-NC-Pad2)") (class "Default")
      (node (ref "U3") (pin "2") (pinfunction "NC_2") (pintype "unspecified+no_connect"))
    )
    (net (code "102") (name "unconnected-(U3-NC-Pad3)") (class "Default")
      (node (ref "U3") (pin "3") (pinfunction "NC_3") (pintype "unspecified+no_connect"))
    )
    (net (code "103") (name "unconnected-(U3-NC-Pad4)") (class "Default")
      (node (ref "U3") (pin "4") (pinfunction "NC_4") (pintype "unspecified+no_connect"))
    )
    (net (code "104") (name "unconnected-(U3-NC-Pad5)") (class "Default")
      (node (ref "U3") (pin "5") (pinfunction "NC_5") (pintype "unspecified+no_connect"))
    )
    (net (code "105") (name "unconnected-(U3-NC-Pad14)") (class "Default")
      (node (ref "U3") (pin "14") (pinfunction "NC_14") (pintype "unspecified+no_connect"))
    )
    (net (code "106") (name "unconnected-(U3-NC-Pad15)") (class "Default")
      (node (ref "U3") (pin "15") (pinfunction "NC_15") (pintype "unspecified+no_connect"))
    )
    (net (code "107") (name "unconnected-(U3-NC-Pad16)") (class "Default")
      (node (ref "U3") (pin "16") (pinfunction "NC_16") (pintype "unspecified+no_connect"))
    )
    (net (code "108") (name "unconnected-(U3-NC-Pad17)") (class "Default")
      (node (ref "U3") (pin "17") (pinfunction "NC_17") (pintype "unspecified+no_connect"))
    )
    (net (code "109") (name "unconnected-(U3-RESV-Pad19)") (class "Default")
      (node (ref "U3") (pin "19") (pinfunction "RESV_19") (pintype "unspecified+no_connect"))
    )
    (net (code "110") (name "unconnected-(U3-RESV-Pad21)") (class "Default")
      (node (ref "U3") (pin "21") (pinfunction "RESV_21") (pintype "unspecified+no_connect"))
    )
    (net (code "111") (name "unconnected-(U3-RESV-Pad22)") (class "Default")
      (node (ref "U3") (pin "22") (pinfunction "RESV_22") (pintype "unspecified+no_connect"))
    )
    (net (code "112") (name "unconnected-(U3-VLOGIC-Pad8)") (class "Default")
      (node (ref "U3") (pin "8") (pinfunction "VLOGIC_8") (pintype "unspecified+no_connect"))
    )
    (net (code "113") (name "unconnected-(U5-EN-Pad3)") (class "Default")
      (node (ref "U5") (pin "3") (pinfunction "EN_3") (pintype "unspecified+no_connect"))
    )
    (net (code "114") (name "unconnected-(U5-EP-Pad9)") (class "Default")
      (node (ref "U5") (pin "9") (pinfunction "EP_9") (pintype "unspecified+no_connect"))
    )
    (net (code "115") (name "unconnected-(U6-ID-Pad4)") (class "Default")
      (node (ref "U6") (pin "4") (pinfunction "ID_4") (pintype "unspecified+no_connect"))
    )
    (net (code "116") (name "unconnected-(U33-Pad0)") (class "Default")
      (node (ref "U33") (pin "0") (pinfunction "0_0") (pintype "unspecified+no_connect"))
    )
    (net (code "117") (name "unconnected-(U33-PadCD)") (class "Default")
      (node (ref "U33") (pin "CD") (pinfunction "CD_CD") (pintype "unspecified+no_connect"))
    )
  )
)
